# SCH_ESP32-S3_Project_2025-03-01.net
KiCad netlist of a schematic drawn in EasyEDA
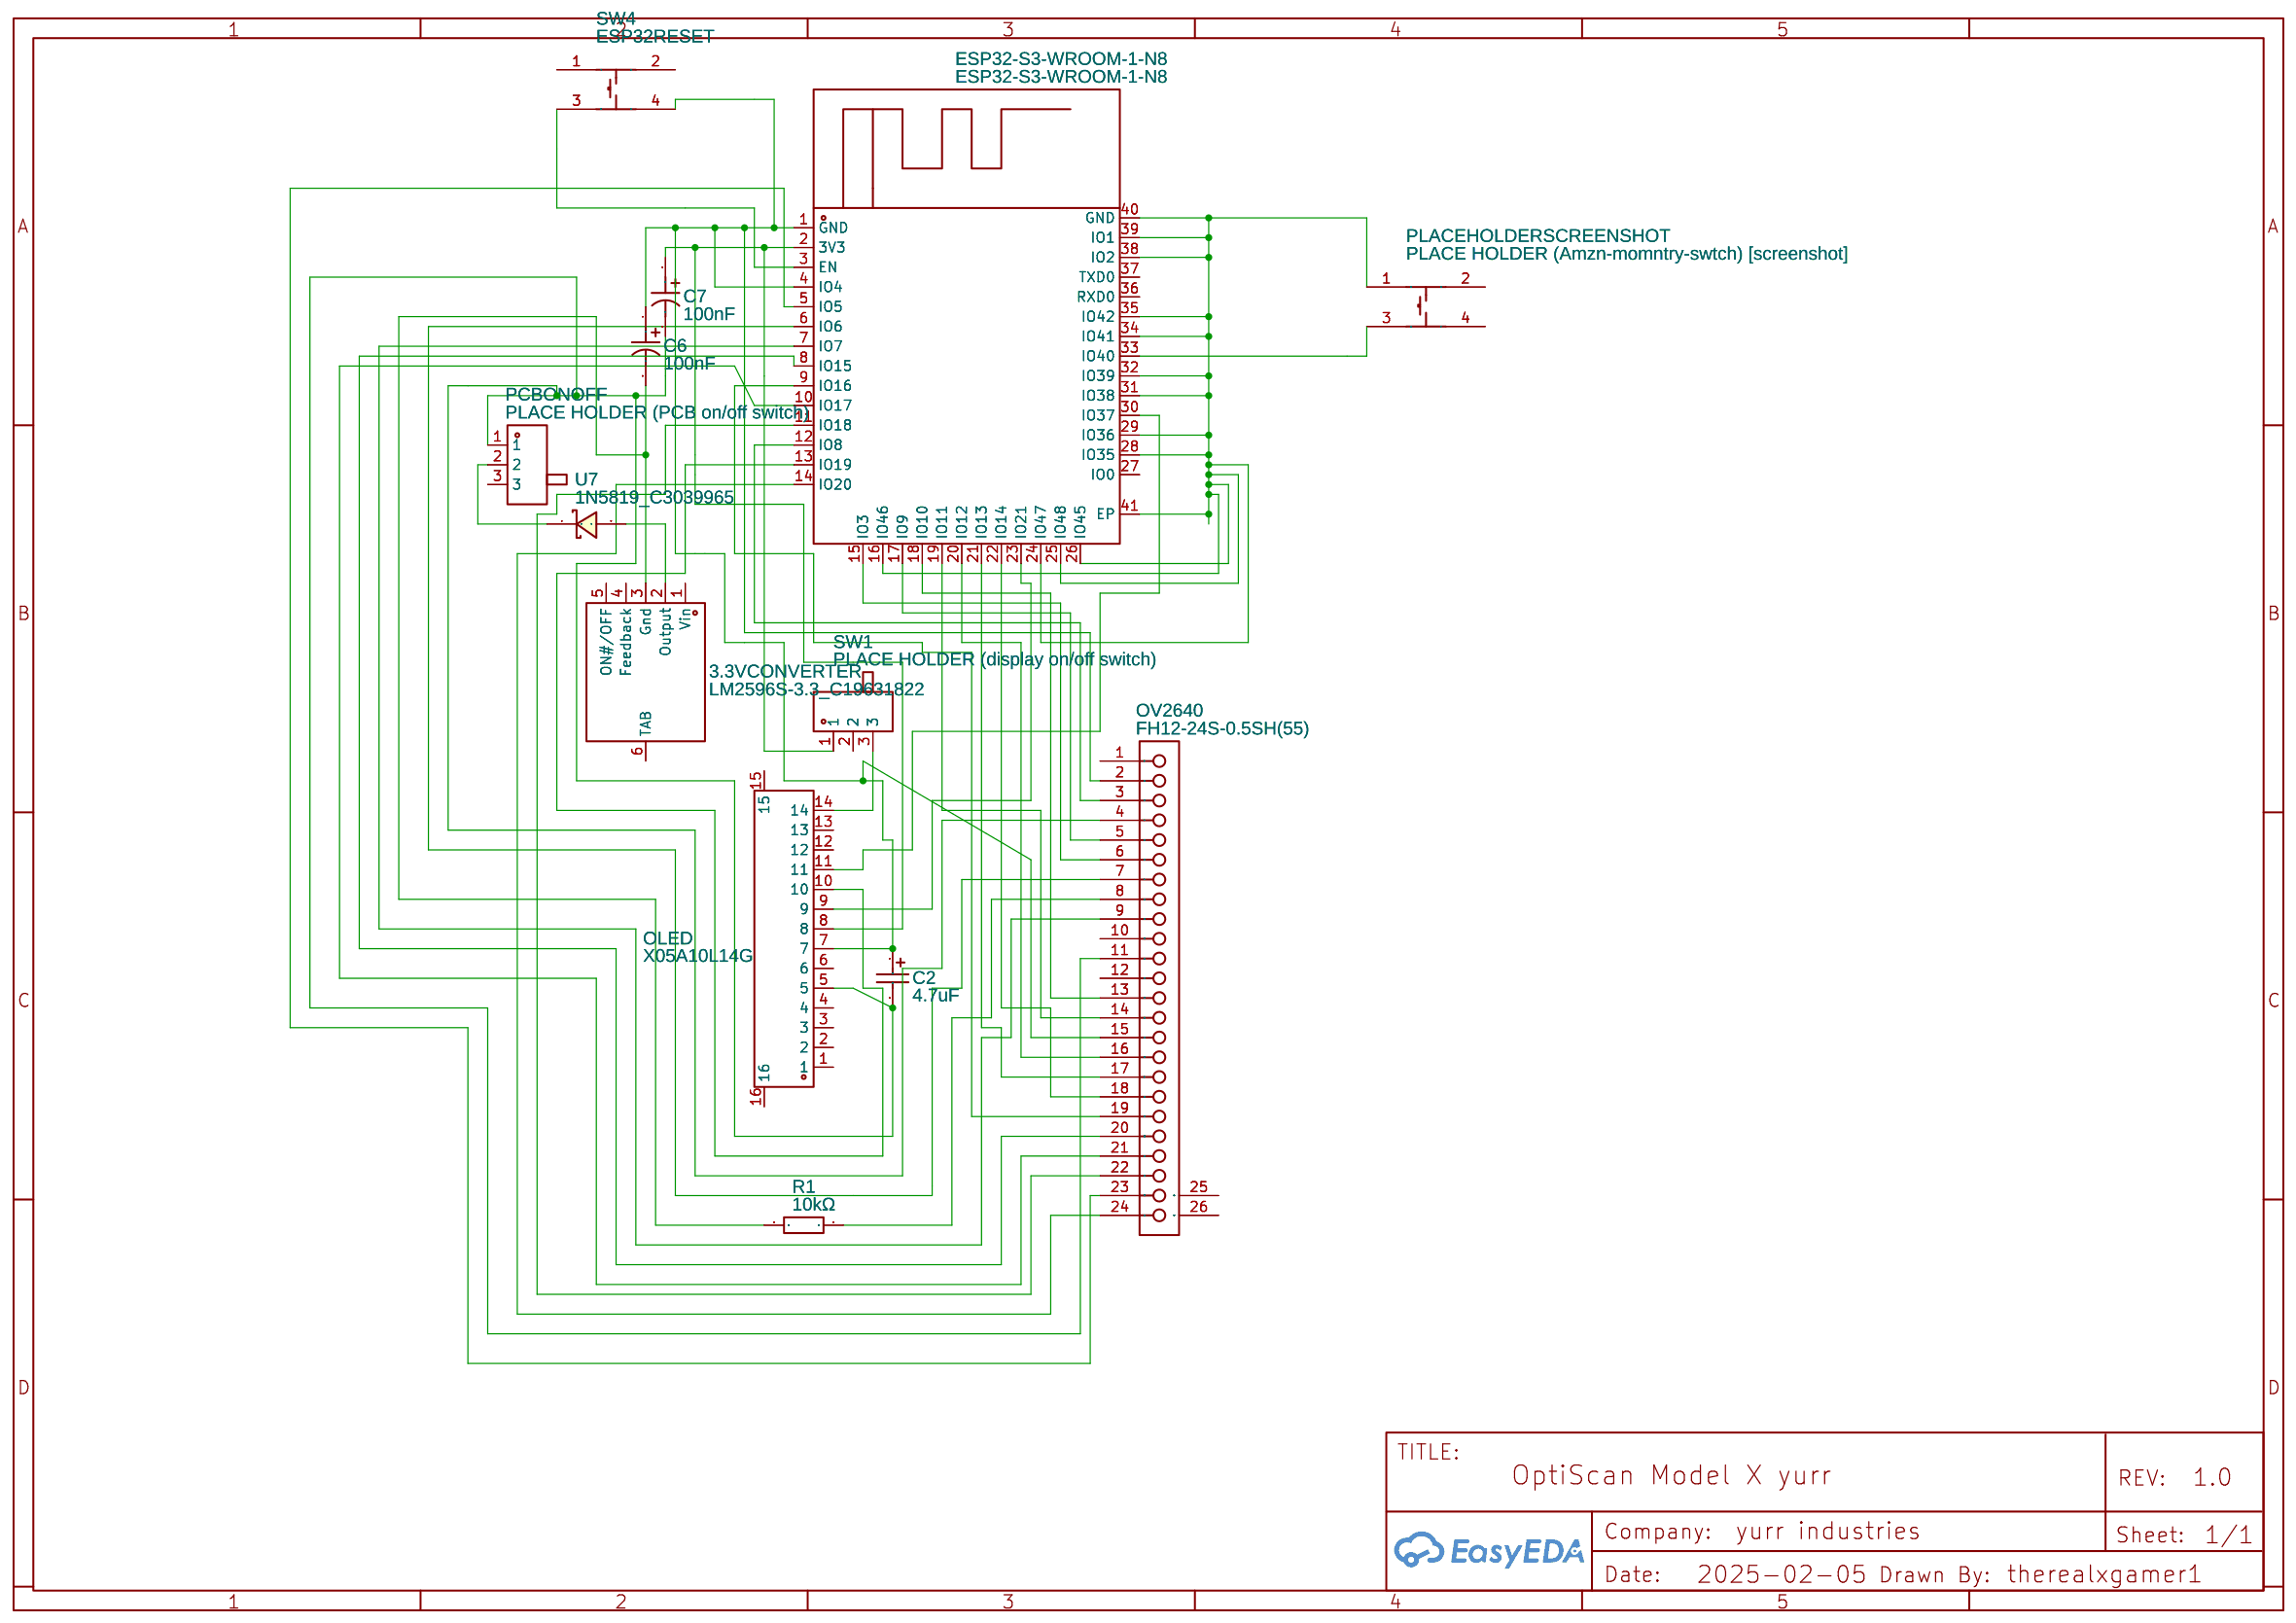
[diagram p0: schematic sheet]

(export (version "E")
  (design (tool "Eeschema 10.0.6"))
  (components
    (comp (ref "3.3VCONVERTER")
      (value "LM2596S-3.3_C19631822")
      (fields (field (name "Manufacturer Part") "LM2596S-3.3") (field (name "Manufacturer") "GR(国睿)"))
      (libsource (lib "") (part "LM2596S-3.3_C19631822"))
    )
    (comp (ref "C2")
      (value "4.7uF")
      (fields (field (name "Manufacturer Part") "CA45-A016K475T") (field (name "Manufacturer") "湘怡中元/湘江"))
      (libsource (lib "") (part "CA45-A016K475T"))
    )
    (comp (ref "C6")
      (value "100nF")
      (fields (field (name "Manufacturer Part") "T491A104M050AT") (field (name "Manufacturer") "KEMET(基美)"))
      (libsource (lib "") (part "T491A104M050AT"))
    )
    (comp (ref "C7")
      (value "100nF")
      (fields (field (name "Manufacturer Part") "T491A104M050AT") (field (name "Manufacturer") "KEMET(基美)"))
      (libsource (lib "") (part "T491A104M050AT"))
    )
    (comp (ref "ESP32-S3-WROOM-1-N8")
      (value "ESP32-S3-WROOM-1-N8")
      (fields (field (name "Manufacturer") "ESPRESSIF(乐鑫)"))
      (libsource (lib "") (part "ESP32-S3-WROOM-1-N8"))
    )
    (comp (ref "OLED")
      (value "X05A10L14G")
      (fields (field (name "Manufacturer") "XKB Connection(中国星坤)"))
      (libsource (lib "") (part "X05A10L14G"))
    )
    (comp (ref "OV2640")
      (value "FH12-24S-0.5SH(55)")
      (fields (field (name "Manufacturer") "HRS(广濑)"))
      (libsource (lib "") (part "FH12-24S-0.5SH(55)"))
    )
    (comp (ref "PCBONOFF")
      (value "PLACE HOLDER (PCB on/off switch)")
      (fields
        (field (name "Manufacturer Part") "SK-3245S-L4-A")
        (field (name "Manufacturer") "XKB Connection(中国星坤)")
      )
      (libsource (lib "") (part "SK-3245S-L4-A"))
    )
    (comp (ref "PLACEHOLDERSCREENSHOT")
      (value "PLACE HOLDER (Amzn-momntry-swtch) [screenshot]")
      (fields (field (name "Manufacturer Part") "TS-1002S-06026C") (field (name "Manufacturer") "XUNPU(讯普)"))
      (libsource (lib "") (part "TS-1002S-06026C"))
    )
    (comp (ref "R1")
      (value "10kΩ")
      (fields
        (field (name "Manufacturer Part") "1206W4F1002T5E")
        (field (name "Manufacturer") "UNI-ROYAL(厚声)")
      )
      (libsource (lib "") (part "1206W4F1002T5E"))
    )
    (comp (ref "SW1")
      (value "PLACE HOLDER (display on/off switch)")
      (fields
        (field (name "Manufacturer Part") "SK-3245S-L4-A")
        (field (name "Manufacturer") "XKB Connection(中国星坤)")
      )
      (libsource (lib "") (part "SK-3245S-L4-A_1"))
    )
    (comp (ref "SW4")
      (value "ESP32RESET")
      (fields (field (name "Manufacturer Part") "TS-1002S-06026C") (field (name "Manufacturer") "XUNPU(讯普)"))
      (libsource (lib "") (part "TS-1002S-06026C_1"))
    )
    (comp (ref "U7")
      (value "1N5819_C3039965")
      (fields (field (name "Manufacturer Part") "1N5819") (field (name "Manufacturer") "YFW(佑风微)"))
      (libsource (lib "") (part "1N5819_C3039965"))
    )
  )
  (nets
    (net (code "1") (name "Net-(3.3VCONVERTER-Gnd)") (class "Default")
      (node (ref "3.3VCONVERTER") (pin "3") (pinfunction "Gnd_3") (pintype "unspecified"))
      (node (ref "C6") (pin "2") (pinfunction "2_2") (pintype "input"))
      (node (ref "R1") (pin "2") (pinfunction "2_2") (pintype "input"))
    )
    (net (code "2") (name "Net-(3.3VCONVERTER-Output)") (class "Default")
      (node (ref "3.3VCONVERTER") (pin "2") (pinfunction "Output_2") (pintype "unspecified"))
      (node (ref "U7") (pin "2") (pinfunction "A_2") (pintype "unspecified"))
    )
    (net (code "3") (name "Net-(C2-Pad2)") (class "Default")
      (node (ref "C2") (pin "2") (pinfunction "2_2") (pintype "input"))
      (node (ref "C7") (pin "2") (pinfunction "2_2") (pintype "input"))
      (node (ref "OLED") (pin "5") (pinfunction "5_5") (pintype "unspecified"))
      (node (ref "OV2640") (pin "11") (pinfunction "11_11") (pintype "unspecified"))
      (node (ref "OV2640") (pin "4") (pinfunction "4_4") (pintype "unspecified"))
      (node (ref "PCBONOFF") (pin "1") (pinfunction "1_1") (pintype "unspecified"))
    )
    (net (code "4") (name "Net-(ESP32-S3-WROOM-1-N8-3V3)") (class "Default")
      (node (ref "C7") (pin "1") (pinfunction "1_1") (pintype "input"))
      (node (ref "ESP32-S3-WROOM-1-N8") (pin "2") (pinfunction "3V3_2") (pintype "unspecified"))
      (node (ref "OLED") (pin "8") (pinfunction "8_8") (pintype "unspecified"))
      (node (ref "SW1") (pin "1") (pinfunction "1_1") (pintype "unspecified"))
    )
    (net (code "5") (name "Net-(ESP32-S3-WROOM-1-N8-EN)") (class "Default")
      (node (ref "ESP32-S3-WROOM-1-N8") (pin "3") (pinfunction "EN_3") (pintype "unspecified"))
      (node (ref "SW4") (pin "3") (pinfunction "3_3") (pintype "unspecified"))
    )
    (net (code "6") (name "Net-(ESP32-S3-WROOM-1-N8-EP)") (class "Default")
      (node (ref "ESP32-S3-WROOM-1-N8") (pin "16") (pinfunction "IO46_16") (pintype "unspecified"))
      (node (ref "ESP32-S3-WROOM-1-N8") (pin "24") (pinfunction "IO47_24") (pintype "unspecified"))
      (node (ref "ESP32-S3-WROOM-1-N8") (pin "25") (pinfunction "IO48_25") (pintype "unspecified"))
      (node (ref "ESP32-S3-WROOM-1-N8") (pin "26") (pinfunction "IO45_26") (pintype "unspecified"))
      (node (ref "ESP32-S3-WROOM-1-N8") (pin "28") (pinfunction "IO35_28") (pintype "unspecified"))
      (node (ref "ESP32-S3-WROOM-1-N8") (pin "29") (pinfunction "IO36_29") (pintype "unspecified"))
      (node (ref "ESP32-S3-WROOM-1-N8") (pin "31") (pinfunction "IO38_31") (pintype "unspecified"))
      (node (ref "ESP32-S3-WROOM-1-N8") (pin "32") (pinfunction "IO39_32") (pintype "unspecified"))
      (node (ref "ESP32-S3-WROOM-1-N8") (pin "34") (pinfunction "IO41_34") (pintype "unspecified"))
      (node (ref "ESP32-S3-WROOM-1-N8") (pin "35") (pinfunction "IO42_35") (pintype "unspecified"))
      (node (ref "ESP32-S3-WROOM-1-N8") (pin "38") (pinfunction "IO2_38") (pintype "unspecified"))
      (node (ref "ESP32-S3-WROOM-1-N8") (pin "39") (pinfunction "IO1_39") (pintype "unspecified"))
      (node (ref "ESP32-S3-WROOM-1-N8") (pin "40") (pinfunction "GND_40") (pintype "unspecified"))
      (node (ref "ESP32-S3-WROOM-1-N8") (pin "41") (pinfunction "EP_41") (pintype "unspecified"))
      (node (ref "PLACEHOLDERSCREENSHOT") (pin "1") (pinfunction "1_1") (pintype "unspecified"))
    )
    (net (code "7") (name "Net-(ESP32-S3-WROOM-1-N8-IO3)") (class "Default")
      (node (ref "ESP32-S3-WROOM-1-N8") (pin "15") (pinfunction "IO3_15") (pintype "unspecified"))
      (node (ref "OV2640") (pin "6") (pinfunction "6_6") (pintype "unspecified"))
    )
    (net (code "8") (name "Net-(ESP32-S3-WROOM-1-N8-IO4)") (class "Default")
      (node (ref "C2") (pin "1") (pinfunction "1_1") (pintype "input"))
      (node (ref "C6") (pin "1") (pinfunction "1_1") (pintype "input"))
      (node (ref "ESP32-S3-WROOM-1-N8") (pin "1") (pinfunction "GND_1") (pintype "unspecified"))
      (node (ref "ESP32-S3-WROOM-1-N8") (pin "4") (pinfunction "IO4_4") (pintype "unspecified"))
      (node (ref "OLED") (pin "7") (pinfunction "7_7") (pintype "unspecified"))
      (node (ref "OV2640") (pin "15") (pinfunction "15_15") (pintype "unspecified"))
      (node (ref "OV2640") (pin "2") (pinfunction "2_2") (pintype "unspecified"))
      (node (ref "SW4") (pin "4") (pinfunction "4_4") (pintype "unspecified"))
    )
    (net (code "9") (name "Net-(ESP32-S3-WROOM-1-N8-IO5)") (class "Default")
      (node (ref "ESP32-S3-WROOM-1-N8") (pin "5") (pinfunction "IO5_5") (pintype "unspecified"))
      (node (ref "OV2640") (pin "23") (pinfunction "23_23") (pintype "unspecified"))
    )
    (net (code "10") (name "Net-(ESP32-S3-WROOM-1-N8-IO6)") (class "Default")
      (node (ref "ESP32-S3-WROOM-1-N8") (pin "6") (pinfunction "IO6_6") (pintype "unspecified"))
      (node (ref "OV2640") (pin "7") (pinfunction "7_7") (pintype "unspecified"))
    )
    (net (code "11") (name "Net-(ESP32-S3-WROOM-1-N8-IO7)") (class "Default")
      (node (ref "ESP32-S3-WROOM-1-N8") (pin "7") (pinfunction "IO7_7") (pintype "unspecified"))
      (node (ref "OV2640") (pin "9") (pinfunction "9_9") (pintype "unspecified"))
    )
    (net (code "12") (name "Net-(ESP32-S3-WROOM-1-N8-IO8)") (class "Default")
      (node (ref "ESP32-S3-WROOM-1-N8") (pin "12") (pinfunction "IO8_12") (pintype "unspecified"))
      (node (ref "OV2640") (pin "3") (pinfunction "3_3") (pintype "unspecified"))
    )
    (net (code "13") (name "Net-(ESP32-S3-WROOM-1-N8-IO9)") (class "Default")
      (node (ref "ESP32-S3-WROOM-1-N8") (pin "17") (pinfunction "IO9_17") (pintype "unspecified"))
      (node (ref "OV2640") (pin "5") (pinfunction "5_5") (pintype "unspecified"))
    )
    (net (code "14") (name "Net-(ESP32-S3-WROOM-1-N8-IO10)") (class "Default")
      (node (ref "ESP32-S3-WROOM-1-N8") (pin "18") (pinfunction "IO10_18") (pintype "unspecified"))
      (node (ref "OV2640") (pin "13") (pinfunction "13_13") (pintype "unspecified"))
    )
    (net (code "15") (name "Net-(ESP32-S3-WROOM-1-N8-IO11)") (class "Default")
      (node (ref "ESP32-S3-WROOM-1-N8") (pin "19") (pinfunction "IO11_19") (pintype "unspecified"))
      (node (ref "OV2640") (pin "14") (pinfunction "14_14") (pintype "unspecified"))
    )
    (net (code "16") (name "Net-(ESP32-S3-WROOM-1-N8-IO12)") (class "Default")
      (node (ref "ESP32-S3-WROOM-1-N8") (pin "20") (pinfunction "IO12_20") (pintype "unspecified"))
      (node (ref "OV2640") (pin "16") (pinfunction "16_16") (pintype "unspecified"))
    )
    (net (code "17") (name "Net-(ESP32-S3-WROOM-1-N8-IO13)") (class "Default")
      (node (ref "ESP32-S3-WROOM-1-N8") (pin "21") (pinfunction "IO13_21") (pintype "unspecified"))
      (node (ref "OV2640") (pin "17") (pinfunction "17_17") (pintype "unspecified"))
    )
    (net (code "18") (name "Net-(ESP32-S3-WROOM-1-N8-IO14)") (class "Default")
      (node (ref "ESP32-S3-WROOM-1-N8") (pin "22") (pinfunction "IO14_22") (pintype "unspecified"))
      (node (ref "OV2640") (pin "18") (pinfunction "18_18") (pintype "unspecified"))
    )
    (net (code "19") (name "Net-(ESP32-S3-WROOM-1-N8-IO15)") (class "Default")
      (node (ref "ESP32-S3-WROOM-1-N8") (pin "8") (pinfunction "IO15_8") (pintype "unspecified"))
      (node (ref "OV2640") (pin "20") (pinfunction "20_20") (pintype "unspecified"))
    )
    (net (code "20") (name "Net-(ESP32-S3-WROOM-1-N8-IO16)") (class "Default")
      (node (ref "ESP32-S3-WROOM-1-N8") (pin "9") (pinfunction "IO16_9") (pintype "unspecified"))
      (node (ref "OV2640") (pin "19") (pinfunction "19_19") (pintype "unspecified"))
    )
    (net (code "21") (name "Net-(ESP32-S3-WROOM-1-N8-IO17)") (class "Default")
      (node (ref "ESP32-S3-WROOM-1-N8") (pin "10") (pinfunction "IO17_10") (pintype "unspecified"))
      (node (ref "OV2640") (pin "21") (pinfunction "21_21") (pintype "unspecified"))
    )
    (net (code "22") (name "Net-(ESP32-S3-WROOM-1-N8-IO18)") (class "Default")
      (node (ref "ESP32-S3-WROOM-1-N8") (pin "11") (pinfunction "IO18_11") (pintype "unspecified"))
      (node (ref "OV2640") (pin "22") (pinfunction "22_22") (pintype "unspecified"))
    )
    (net (code "23") (name "Net-(ESP32-S3-WROOM-1-N8-IO19)") (class "Default")
      (node (ref "ESP32-S3-WROOM-1-N8") (pin "13") (pinfunction "IO19_13") (pintype "unspecified"))
      (node (ref "OLED") (pin "10") (pinfunction "10_10") (pintype "unspecified"))
    )
    (net (code "24") (name "Net-(ESP32-S3-WROOM-1-N8-IO20)") (class "Default")
      (node (ref "ESP32-S3-WROOM-1-N8") (pin "14") (pinfunction "IO20_14") (pintype "unspecified"))
      (node (ref "OV2640") (pin "24") (pinfunction "24_24") (pintype "unspecified"))
    )
    (net (code "25") (name "Net-(ESP32-S3-WROOM-1-N8-IO21)") (class "Default")
      (node (ref "ESP32-S3-WROOM-1-N8") (pin "23") (pinfunction "IO21_23") (pintype "unspecified"))
      (node (ref "OLED") (pin "9") (pinfunction "9_9") (pintype "unspecified"))
    )
    (net (code "26") (name "Net-(ESP32-S3-WROOM-1-N8-IO37)") (class "Default")
      (node (ref "ESP32-S3-WROOM-1-N8") (pin "30") (pinfunction "IO37_30") (pintype "unspecified"))
      (node (ref "OLED") (pin "11") (pinfunction "11_11") (pintype "unspecified"))
    )
    (net (code "27") (name "Net-(ESP32-S3-WROOM-1-N8-IO40)") (class "Default")
      (node (ref "ESP32-S3-WROOM-1-N8") (pin "33") (pinfunction "IO40_33") (pintype "unspecified"))
      (node (ref "PLACEHOLDERSCREENSHOT") (pin "3") (pinfunction "3_3") (pintype "unspecified"))
    )
    (net (code "28") (name "Net-(OLED-Pad14)") (class "Default")
      (node (ref "OLED") (pin "14") (pinfunction "14_14") (pintype "unspecified"))
      (node (ref "SW1") (pin "3") (pinfunction "3_3") (pintype "unspecified"))
    )
    (net (code "29") (name "Net-(OV2640-Pad8)") (class "Default")
      (node (ref "OV2640") (pin "8") (pinfunction "8_8") (pintype "unspecified"))
      (node (ref "R1") (pin "1") (pinfunction "1_1") (pintype "input"))
    )
    (net (code "30") (name "Net-(U7-K)") (class "Default")
      (node (ref "PCBONOFF") (pin "2") (pinfunction "2_2") (pintype "unspecified"))
      (node (ref "U7") (pin "1") (pinfunction "K_1") (pintype "unspecified"))
    )
    (net (code "31") (name "unconnected-(3.3VCONVERTER-Feedback-Pad4)") (class "Default")
      (node (ref "3.3VCONVERTER") (pin "4") (pinfunction "Feedback_4") (pintype "unspecified"))
    )
    (net (code "32") (name "unconnected-(3.3VCONVERTER-ON#{slash}OFF-Pad5)") (class "Default")
      (node (ref "3.3VCONVERTER") (pin "5") (pinfunction "ON#/OFF_5") (pintype "unspecified"))
    )
    (net (code "33") (name "unconnected-(3.3VCONVERTER-TAB-Pad6)") (class "Default")
      (node (ref "3.3VCONVERTER") (pin "6") (pinfunction "TAB_6") (pintype "unspecified"))
    )
    (net (code "34") (name "unconnected-(3.3VCONVERTER-Vin-Pad1)") (class "Default")
      (node (ref "3.3VCONVERTER") (pin "1") (pinfunction "Vin_1") (pintype "unspecified"))
    )
    (net (code "35") (name "unconnected-(ESP32-S3-WROOM-1-N8-IO0-Pad27)") (class "Default")
      (node (ref "ESP32-S3-WROOM-1-N8") (pin "27") (pinfunction "IO0_27") (pintype "unspecified"))
    )
    (net (code "36") (name "unconnected-(ESP32-S3-WROOM-1-N8-RXD0-Pad36)") (class "Default")
      (node (ref "ESP32-S3-WROOM-1-N8") (pin "36") (pinfunction "RXD0_36") (pintype "unspecified"))
    )
    (net (code "37") (name "unconnected-(ESP32-S3-WROOM-1-N8-TXD0-Pad37)") (class "Default")
      (node (ref "ESP32-S3-WROOM-1-N8") (pin "37") (pinfunction "TXD0_37") (pintype "unspecified"))
    )
    (net (code "38") (name "unconnected-(OLED-Pad1)") (class "Default")
      (node (ref "OLED") (pin "1") (pinfunction "1_1") (pintype "unspecified"))
    )
    (net (code "39") (name "unconnected-(OLED-Pad2)") (class "Default")
      (node (ref "OLED") (pin "2") (pinfunction "2_2") (pintype "unspecified"))
    )
    (net (code "40") (name "unconnected-(OLED-Pad3)") (class "Default")
      (node (ref "OLED") (pin "3") (pinfunction "3_3") (pintype "unspecified"))
    )
    (net (code "41") (name "unconnected-(OLED-Pad4)") (class "Default")
      (node (ref "OLED") (pin "4") (pinfunction "4_4") (pintype "unspecified"))
    )
    (net (code "42") (name "unconnected-(OLED-Pad6)") (class "Default")
      (node (ref "OLED") (pin "6") (pinfunction "6_6") (pintype "unspecified"))
    )
    (net (code "43") (name "unconnected-(OLED-Pad12)") (class "Default")
      (node (ref "OLED") (pin "12") (pinfunction "12_12") (pintype "unspecified"))
    )
    (net (code "44") (name "unconnected-(OLED-Pad13)") (class "Default")
      (node (ref "OLED") (pin "13") (pinfunction "13_13") (pintype "unspecified"))
    )
    (net (code "45") (name "unconnected-(OLED-Pad15)") (class "Default")
      (node (ref "OLED") (pin "15") (pinfunction "15_15") (pintype "unspecified"))
    )
    (net (code "46") (name "unconnected-(OLED-Pad16)") (class "Default")
      (node (ref "OLED") (pin "16") (pinfunction "16_16") (pintype "unspecified"))
    )
    (net (code "47") (name "unconnected-(OV2640-Pad1)") (class "Default")
      (node (ref "OV2640") (pin "1") (pinfunction "1_1") (pintype "unspecified"))
    )
    (net (code "48") (name "unconnected-(OV2640-Pad10)") (class "Default")
      (node (ref "OV2640") (pin "10") (pinfunction "10_10") (pintype "unspecified"))
    )
    (net (code "49") (name "unconnected-(OV2640-Pad12)") (class "Default")
      (node (ref "OV2640") (pin "12") (pinfunction "12_12") (pintype "unspecified"))
    )
    (net (code "50") (name "unconnected-(OV2640-Pad25)") (class "Default")
      (node (ref "OV2640") (pin "25") (pinfunction "25_25") (pintype "unspecified"))
    )
    (net (code "51") (name "unconnected-(OV2640-Pad26)") (class "Default")
      (node (ref "OV2640") (pin "26") (pinfunction "26_26") (pintype "unspecified"))
    )
    (net (code "52") (name "unconnected-(PCBONOFF-Pad3)") (class "Default")
      (node (ref "PCBONOFF") (pin "3") (pinfunction "3_3") (pintype "unspecified"))
    )
    (net (code "53") (name "unconnected-(PLACEHOLDERSCREENSHOT-Pad2)") (class "Default")
      (node (ref "PLACEHOLDERSCREENSHOT") (pin "2") (pinfunction "2_2") (pintype "unspecified"))
    )
    (net (code "54") (name "unconnected-(PLACEHOLDERSCREENSHOT-Pad4)") (class "Default")
      (node (ref "PLACEHOLDERSCREENSHOT") (pin "4") (pinfunction "4_4") (pintype "unspecified"))
    )
    (net (code "55") (name "unconnected-(SW1-Pad2)") (class "Default")
      (node (ref "SW1") (pin "2") (pinfunction "2_2") (pintype "unspecified"))
    )
    (net (code "56") (name "unconnected-(SW4-Pad1)") (class "Default")
      (node (ref "SW4") (pin "1") (pinfunction "1_1") (pintype "unspecified"))
    )
    (net (code "57") (name "unconnected-(SW4-Pad2)") (class "Default")
      (node (ref "SW4") (pin "2") (pinfunction "2_2") (pintype "unspecified"))
    )
  )
)
